# 9led-module.net
KiCad netlist of a schematic drawn in EAGLE
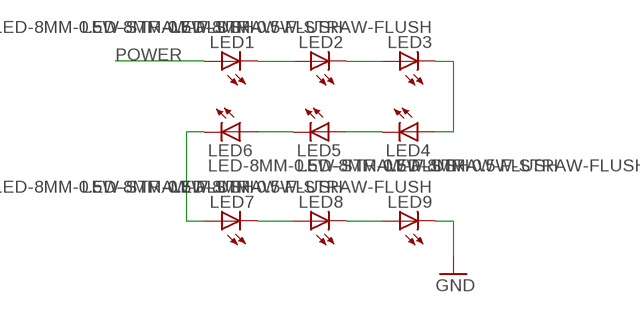
[diagram p0: schematic, sheet 1]

(export (version "E")
  (design (tool "Eeschema 10.0.6"))
  (components
    (comp (ref "LED1")
      (value "LED-8MM-0.5W-STRAW-FLUSH")
      (footprint "eagle-import:LED-8MM-0.5W-FLUSH")
      (libsource (lib "eagle-import") (part "LED-8MM-0.5W-STRAW-FLUSH"))
    )
    (comp (ref "LED2")
      (value "LED-8MM-0.5W-STRAW-FLUSH")
      (footprint "eagle-import:LED-8MM-0.5W-FLUSH")
      (libsource (lib "eagle-import") (part "LED-8MM-0.5W-STRAW-FLUSH"))
    )
    (comp (ref "LED3")
      (value "LED-8MM-0.5W-STRAW-FLUSH")
      (footprint "eagle-import:LED-8MM-0.5W-FLUSH")
      (libsource (lib "eagle-import") (part "LED-8MM-0.5W-STRAW-FLUSH"))
    )
    (comp (ref "LED4")
      (value "LED-8MM-0.5W-STRAW-FLUSH")
      (footprint "eagle-import:LED-8MM-0.5W-FLUSH")
      (libsource (lib "eagle-import") (part "LED-8MM-0.5W-STRAW-FLUSH"))
    )
    (comp (ref "LED5")
      (value "LED-8MM-0.5W-STRAW-FLUSH")
      (footprint "eagle-import:LED-8MM-0.5W-FLUSH")
      (libsource (lib "eagle-import") (part "LED-8MM-0.5W-STRAW-FLUSH"))
    )
    (comp (ref "LED6")
      (value "LED-8MM-0.5W-STRAW-FLUSH")
      (footprint "eagle-import:LED-8MM-0.5W-FLUSH")
      (libsource (lib "eagle-import") (part "LED-8MM-0.5W-STRAW-FLUSH"))
    )
    (comp (ref "LED7")
      (value "LED-8MM-0.5W-STRAW-FLUSH")
      (footprint "eagle-import:LED-8MM-0.5W-FLUSH")
      (libsource (lib "eagle-import") (part "LED-8MM-0.5W-STRAW-FLUSH"))
    )
    (comp (ref "LED8")
      (value "LED-8MM-0.5W-STRAW-FLUSH")
      (footprint "eagle-import:LED-8MM-0.5W-FLUSH")
      (libsource (lib "eagle-import") (part "LED-8MM-0.5W-STRAW-FLUSH"))
    )
    (comp (ref "LED9")
      (value "LED-8MM-0.5W-STRAW-FLUSH")
      (footprint "eagle-import:LED-8MM-0.5W-FLUSH")
      (libsource (lib "eagle-import") (part "LED-8MM-0.5W-STRAW-FLUSH"))
    )
  )
  (nets
    (net (code "1") (name "/POWER") (class "Default")
      (node (ref "LED1") (pin "P$1") (pinfunction "A_P$1") (pintype "passive"))
    )
    (net (code "2") (name "GND") (class "Default")
      (node (ref "LED9") (pin "P$2") (pinfunction "C_P$2") (pintype "passive"))
    )
    (net (code "3") (name "Net-(LED1-C)") (class "Default")
      (node (ref "LED1") (pin "P$2") (pinfunction "C_P$2") (pintype "passive"))
      (node (ref "LED2") (pin "P$1") (pinfunction "A_P$1") (pintype "passive"))
    )
    (net (code "4") (name "Net-(LED2-C)") (class "Default")
      (node (ref "LED2") (pin "P$2") (pinfunction "C_P$2") (pintype "passive"))
      (node (ref "LED3") (pin "P$1") (pinfunction "A_P$1") (pintype "passive"))
    )
    (net (code "5") (name "Net-(LED3-C)") (class "Default")
      (node (ref "LED3") (pin "P$2") (pinfunction "C_P$2") (pintype "passive"))
      (node (ref "LED4") (pin "P$1") (pinfunction "A_P$1") (pintype "passive"))
    )
    (net (code "6") (name "Net-(LED4-C)") (class "Default")
      (node (ref "LED4") (pin "P$2") (pinfunction "C_P$2") (pintype "passive"))
      (node (ref "LED5") (pin "P$1") (pinfunction "A_P$1") (pintype "passive"))
    )
    (net (code "7") (name "Net-(LED5-C)") (class "Default")
      (node (ref "LED5") (pin "P$2") (pinfunction "C_P$2") (pintype "passive"))
      (node (ref "LED6") (pin "P$1") (pinfunction "A_P$1") (pintype "passive"))
    )
    (net (code "8") (name "Net-(LED6-C)") (class "Default")
      (node (ref "LED6") (pin "P$2") (pinfunction "C_P$2") (pintype "passive"))
      (node (ref "LED7") (pin "P$1") (pinfunction "A_P$1") (pintype "passive"))
    )
    (net (code "9") (name "Net-(LED7-C)") (class "Default")
      (node (ref "LED7") (pin "P$2") (pinfunction "C_P$2") (pintype "passive"))
      (node (ref "LED8") (pin "P$1") (pinfunction "A_P$1") (pintype "passive"))
    )
    (net (code "10") (name "Net-(LED8-C)") (class "Default")
      (node (ref "LED8") (pin "P$2") (pinfunction "C_P$2") (pintype "passive"))
      (node (ref "LED9") (pin "P$1") (pinfunction "A_P$1") (pintype "passive"))
    )
  )
)
